# Multivib_Sheet1.net
KiCad netlist of a schematic drawn in Altium Designer
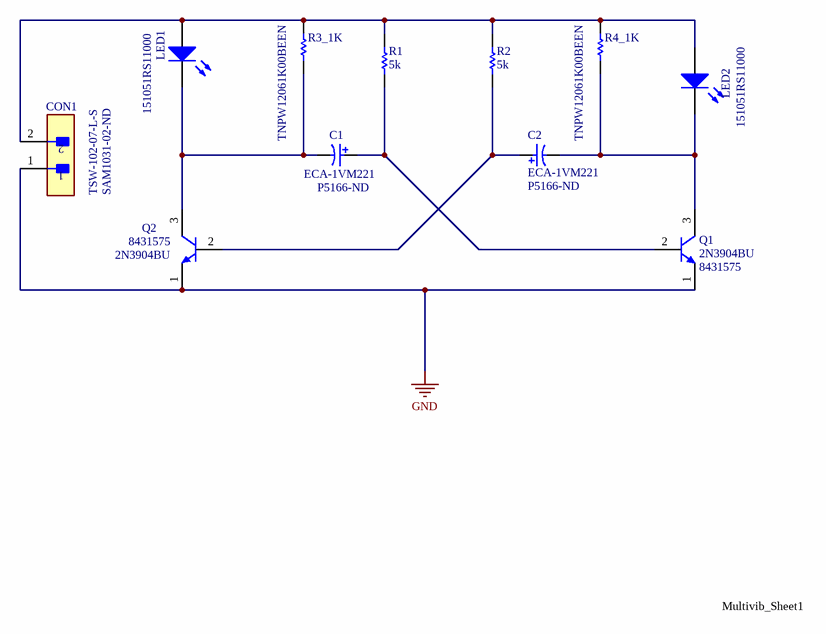
[diagram p0: Multivib_Sheet1.SchDoc]

(export (version "E")
  (design (tool "Eeschema 10.0.6"))
  (components
    (comp (ref "C1")
      (value "ECA-1VM221")
      (footprint "PNSC-ECA-1VM221-2")
      (description "Aluminum Electrolytic Capacitor, 220 uF, +/- 20%, 35 V, -40 to 85 degC, 2-Pin THD, RoHS, Bulk")
      (fields
        (field (name "MANUFACTURER") "Panasonic")
        (field (name "SUPPLIER PART NUMBER 1") "P5166-ND")
        (field (name "TOLERANCE") "20%")
      )
      (libsource (lib "Altium Content Vault") (part "CAP-P-2"))
    )
    (comp (ref "C2")
      (value "ECA-1VM221")
      (footprint "PNSC-ECA-1VM221-2")
      (description "Aluminum Electrolytic Capacitor, 220 uF, +/- 20%, 35 V, -40 to 85 degC, 2-Pin THD, RoHS, Bulk")
      (fields
        (field (name "MANUFACTURER") "Panasonic")
        (field (name "SUPPLIER PART NUMBER 1") "P5166-ND")
        (field (name "TOLERANCE") "20%")
      )
      (libsource (lib "Altium Content Vault") (part "CAP-P-2"))
    )
    (comp (ref "CON1")
      (value "TSW-102-07-L-S")
      (footprint "FP-TSW-102-07-L-S-MFG")
      (description "CONN HEADER VERT 2POS 2.54MM")
      (fields (field (name "SUPPLIER PART NUMBER 1") "SAM1031-02-ND"))
      (libsource (lib "Altium Content Vault") (part "3bc925449376181038e59eaffc5286c"))
    )
    (comp (ref "LED1")
      (value "151051RS11000")
      (footprint "Type 5mm")
      (description "THT LED round mono-color color lens, WL-TMRW, Red")
      (fields (field (name "MANUFACTURER") "Wuerth Elektronik"))
      (libsource (lib "Altium Content Vault") (part "WE-LED_K1A2-2"))
    )
    (comp (ref "LED2")
      (value "151051RS11000")
      (footprint "Type 5mm")
      (description "THT LED round mono-color color lens, WL-TMRW, Red")
      (fields (field (name "MANUFACTURER") "Wuerth Elektronik"))
      (libsource (lib "Altium Content Vault") (part "WE-LED_K1A2-2"))
    )
    (comp (ref "Q1")
      (value "2N3904BU")
      (footprint "FAIR-TO-92")
      (description "NPN General-Purpose Amplifier, 40 V VCEO, 0.2 A, -55 to 150 degC, 2-Pin TO-92, RoHS, Bulk")
      (fields
        (field (name "MANUFACTURER") "FairchildSemiconductor")
        (field (name "SUPPLIER PART NUMBER 1") "8431575")
      )
      (libsource (lib "Altium Content Vault") (part "NPN-E1B2C3-3"))
    )
    (comp (ref "Q2")
      (value "2N3904BU")
      (footprint "FAIR-TO-92")
      (description "NPN General-Purpose Amplifier, 40 V VCEO, 0.2 A, -55 to 150 degC, 2-Pin TO-92, RoHS, Bulk")
      (fields
        (field (name "MANUFACTURER") "FairchildSemiconductor")
        (field (name "SUPPLIER PART NUMBER 1") "8431575")
      )
      (libsource (lib "Altium Content Vault") (part "NPN-E1B2C3-3"))
    )
    (comp (ref "R1")
      (value "5k")
      (footprint "RESC2013X50X30ML20T20")
      (description "Res Thick Film 0805 5K Ohm 1% 1/8W ±100ppm/°C Molded SMD SMD Paper T/R")
      (fields (field (name "PART NUMBER") "CRCW08055K00FKTA") (field (name "MANUFACTURER") "Vishay Dale"))
      (libsource (lib "Altium Content Vault") (part "RES"))
    )
    (comp (ref "R2")
      (value "5k")
      (footprint "RESC2013X50X30ML20T20")
      (description "Res Thick Film 0805 5K Ohm 1% 1/8W ±100ppm/°C Molded SMD SMD Paper T/R")
      (fields (field (name "PART NUMBER") "CRCW08055K00FKTA") (field (name "MANUFACTURER") "Vishay Dale"))
      (libsource (lib "Altium Content Vault") (part "RES"))
    )
    (comp (ref "R3_1K")
      (value "~")
      (footprint "RESC3216X65X50ML15T25")
      (fields
        (field (name "PART NUMBER") "TNPW12061K00BEEN")
        (field (name "MANUFACTURER") "Vishay Dale")
        (field (name "SUPPLIER PART NUMBER 1") "TNPW12061K00BEEN")
        (field (name "TOLERANCE") "0.1%")
      )
      (libsource (lib "Altium Content Vault") (part "RES"))
    )
    (comp (ref "R4_1K")
      (value "~")
      (footprint "RESC3216X65X50ML15T25")
      (fields
        (field (name "PART NUMBER") "TNPW12061K00BEEN")
        (field (name "MANUFACTURER") "Vishay Dale")
        (field (name "SUPPLIER PART NUMBER 1") "TNPW12061K00BEEN")
        (field (name "TOLERANCE") "0.1%")
      )
      (libsource (lib "Altium Content Vault") (part "RES"))
    )
  )
  (nets
    (net (code "1") (name "GND") (class "Default")
      (node (ref "CON1") (pin "1") (pinfunction "1_1") (pintype "passive"))
      (node (ref "Q1") (pin "1") (pinfunction "E_1") (pintype "passive"))
      (node (ref "Q2") (pin "1") (pinfunction "E_1") (pintype "passive"))
    )
    (net (code "2") (name "Net-(LED1-A)") (class "Default")
      (node (ref "CON1") (pin "2") (pinfunction "2_2") (pintype "passive"))
      (node (ref "LED1") (pin "2") (pinfunction "A_2") (pintype "passive"))
      (node (ref "LED2") (pin "2") (pinfunction "A_2") (pintype "passive"))
      (node (ref "R1") (pin "2") (pinfunction "2_2") (pintype "passive"))
      (node (ref "R2") (pin "2") (pinfunction "2_2") (pintype "passive"))
      (node (ref "R3_1K") (pin "2") (pinfunction "2_2") (pintype "passive"))
      (node (ref "R4_1K") (pin "2") (pinfunction "2_2") (pintype "passive"))
    )
    (net (code "3") (name "Net-(LED1-K)") (class "Default")
      (node (ref "C1") (pin "2") (pinfunction "2_2") (pintype "passive"))
      (node (ref "LED1") (pin "1") (pinfunction "K_1") (pintype "passive"))
      (node (ref "Q2") (pin "3") (pinfunction "C_3") (pintype "passive"))
      (node (ref "R3_1K") (pin "1") (pinfunction "1_1") (pintype "passive"))
    )
    (net (code "4") (name "Net-(LED2-K)") (class "Default")
      (node (ref "C2") (pin "2") (pinfunction "2_2") (pintype "passive"))
      (node (ref "LED2") (pin "1") (pinfunction "K_1") (pintype "passive"))
      (node (ref "Q1") (pin "3") (pinfunction "C_3") (pintype "passive"))
      (node (ref "R4_1K") (pin "1") (pinfunction "1_1") (pintype "passive"))
    )
    (net (code "5") (name "Net-(Q1-B)") (class "Default")
      (node (ref "C1") (pin "1") (pinfunction "1_1") (pintype "passive"))
      (node (ref "Q1") (pin "2") (pinfunction "B_2") (pintype "passive"))
      (node (ref "R1") (pin "1") (pinfunction "1_1") (pintype "passive"))
    )
    (net (code "6") (name "Net-(Q2-B)") (class "Default")
      (node (ref "C2") (pin "1") (pinfunction "1_1") (pintype "passive"))
      (node (ref "Q2") (pin "2") (pinfunction "B_2") (pintype "passive"))
      (node (ref "R2") (pin "1") (pinfunction "1_1") (pintype "passive"))
    )
  )
)
